# Explorer.net
KiCad netlist of a schematic drawn in EAGLE
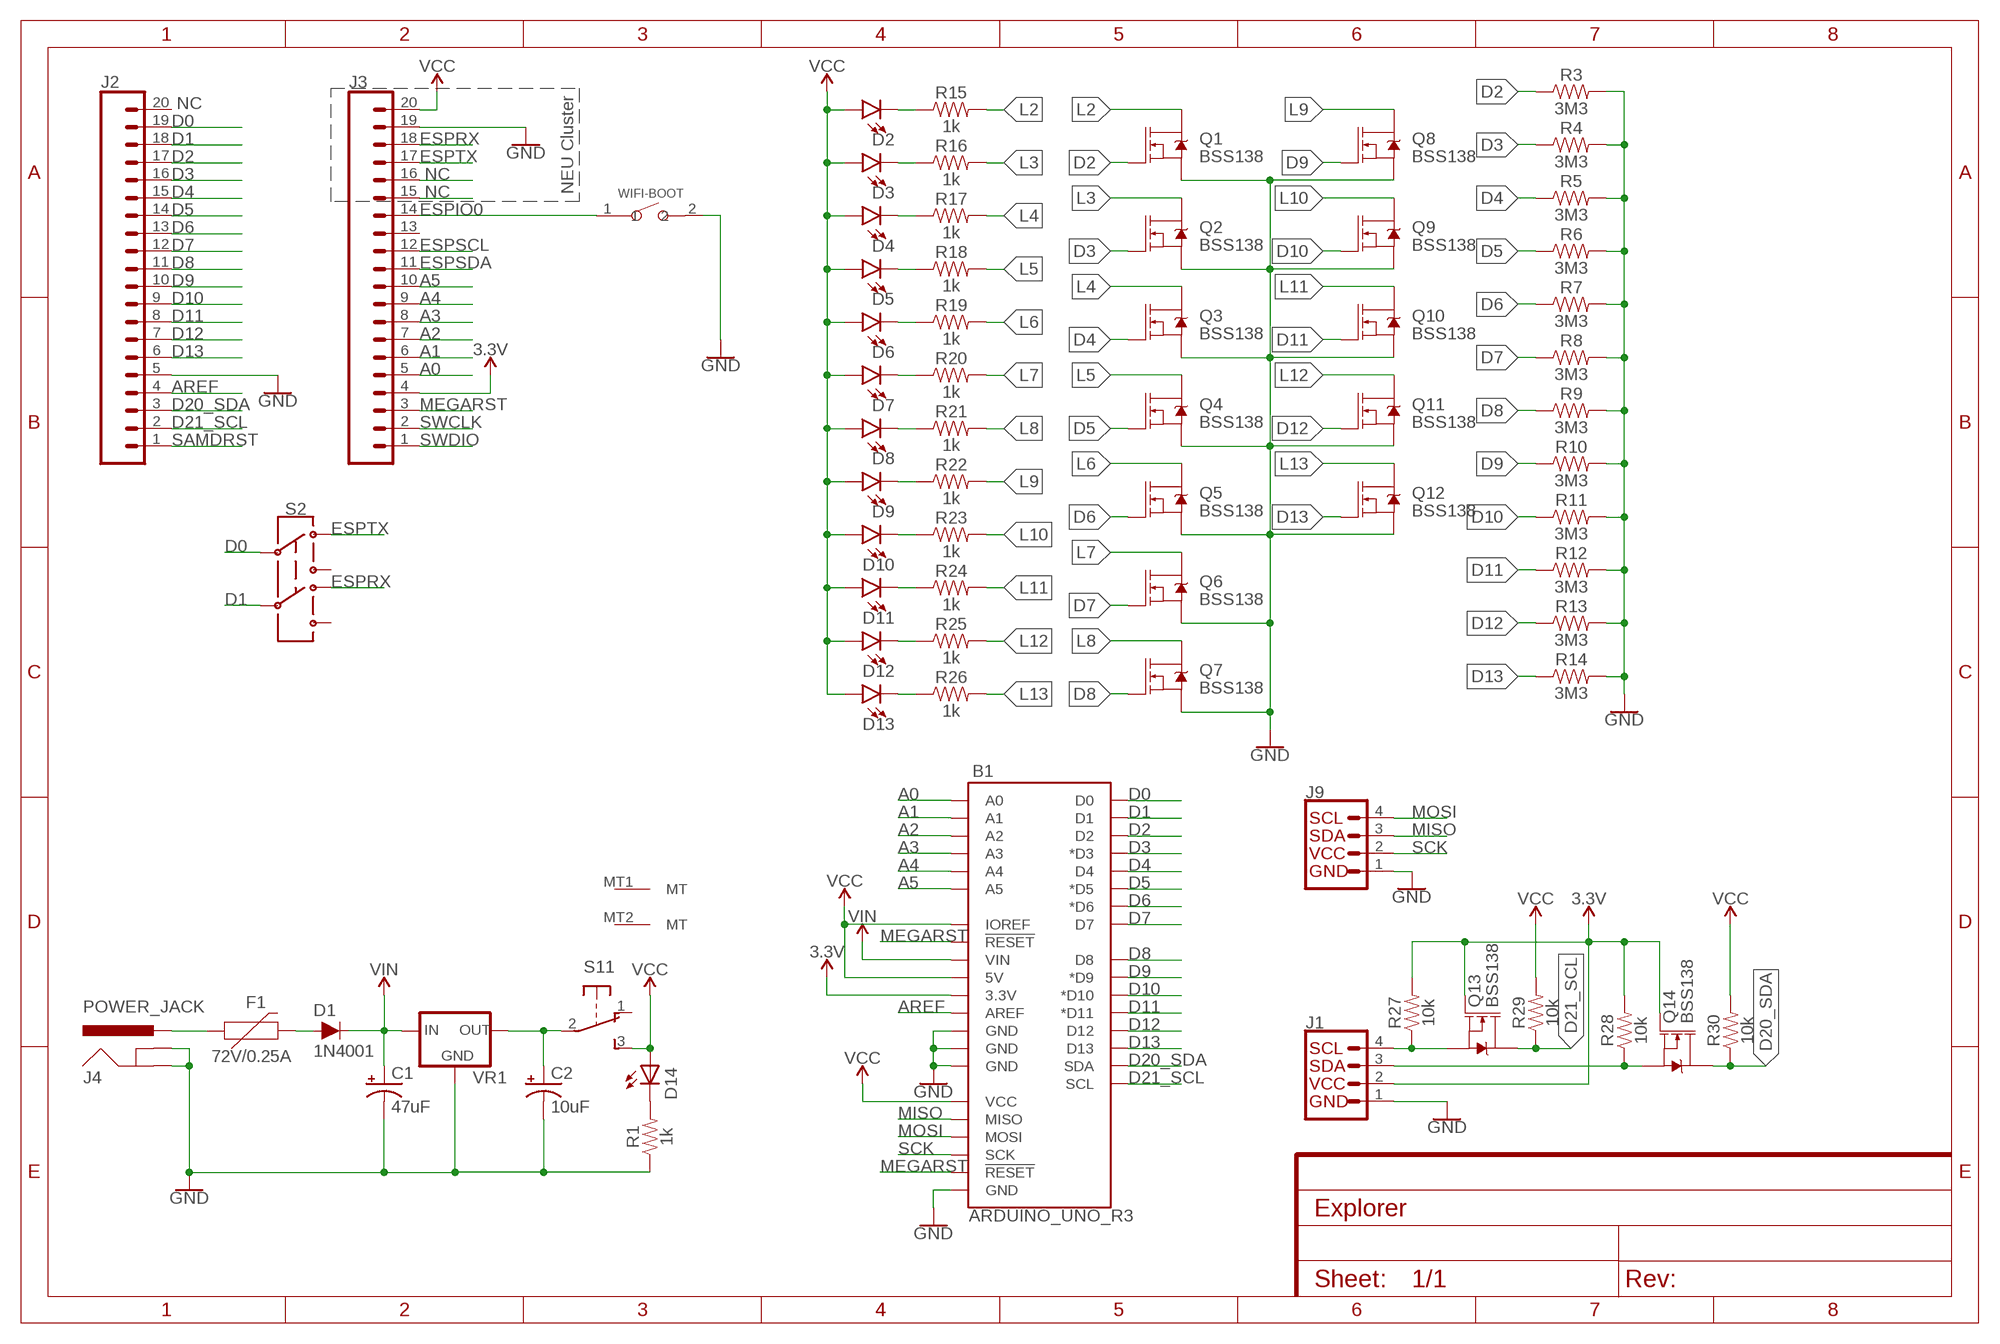
[diagram p0: schematic, sheet 1]

(export (version "E")
  (design (tool "Eeschema 10.0.6"))
  (components
    (comp (ref "B1")
      (value "ARDUINO_UNO_R3")
      (footprint "eagle-import:ARDUINO_R3")
      (libsource (lib "eagle-import") (part "ARDUINO_UNO_R3"))
    )
    (comp (ref "C1")
      (value "47uF")
      (footprint "eagle-import:CPOL-RADIAL-2.5MM-6.5MM")
      (libsource (lib "eagle-import") (part "100UF-POLAR-RADIAL-2.5MM-25V-20%"))
    )
    (comp (ref "C2")
      (value "10uF")
      (footprint "eagle-import:CPOL-RADIAL-2.5MM-6.5MM")
      (libsource (lib "eagle-import") (part "100UF-POLAR-RADIAL-2.5MM-25V-20%"))
    )
    (comp (ref "D1")
      (value "1N4001")
      (footprint "eagle-import:DIODE-1N4001-KIT")
      (libsource (lib "eagle-import") (part "DIODE-KIT2"))
    )
    (comp (ref "D2")
      (value "LED0603")
      (footprint "eagle-import:LED-0603")
      (fields (field (name "LCSC_PART") "C2286"))
      (libsource (lib "eagle-import") (part "LED0603"))
    )
    (comp (ref "D3")
      (value "LED0603")
      (footprint "eagle-import:LED-0603")
      (fields (field (name "LCSC_PART") "C2286"))
      (libsource (lib "eagle-import") (part "LED0603"))
    )
    (comp (ref "D4")
      (value "LED0603")
      (footprint "eagle-import:LED-0603")
      (fields (field (name "LCSC_PART") "C2286"))
      (libsource (lib "eagle-import") (part "LED0603"))
    )
    (comp (ref "D5")
      (value "LED0603")
      (footprint "eagle-import:LED-0603")
      (fields (field (name "LCSC_PART") "C2286"))
      (libsource (lib "eagle-import") (part "LED0603"))
    )
    (comp (ref "D6")
      (value "LED0603")
      (footprint "eagle-import:LED-0603")
      (fields (field (name "LCSC_PART") "C2286"))
      (libsource (lib "eagle-import") (part "LED0603"))
    )
    (comp (ref "D7")
      (value "LED0603")
      (footprint "eagle-import:LED-0603")
      (fields (field (name "LCSC_PART") "C2286"))
      (libsource (lib "eagle-import") (part "LED0603"))
    )
    (comp (ref "D8")
      (value "LED0603")
      (footprint "eagle-import:LED-0603")
      (fields (field (name "LCSC_PART") "C2286"))
      (libsource (lib "eagle-import") (part "LED0603"))
    )
    (comp (ref "D9")
      (value "LED0603")
      (footprint "eagle-import:LED-0603")
      (fields (field (name "LCSC_PART") "C2286"))
      (libsource (lib "eagle-import") (part "LED0603"))
    )
    (comp (ref "D10")
      (value "LED0603")
      (footprint "eagle-import:LED-0603")
      (fields (field (name "LCSC_PART") "C2286"))
      (libsource (lib "eagle-import") (part "LED0603"))
    )
    (comp (ref "D11")
      (value "LED0603")
      (footprint "eagle-import:LED-0603")
      (fields (field (name "LCSC_PART") "C2286"))
      (libsource (lib "eagle-import") (part "LED0603"))
    )
    (comp (ref "D12")
      (value "LED0603")
      (footprint "eagle-import:LED-0603")
      (fields (field (name "LCSC_PART") "C2286"))
      (libsource (lib "eagle-import") (part "LED0603"))
    )
    (comp (ref "D13")
      (value "LED0603")
      (footprint "eagle-import:LED-0603")
      (fields (field (name "LCSC_PART") "C2286"))
      (libsource (lib "eagle-import") (part "LED0603"))
    )
    (comp (ref "D14")
      (value "LEDCHIPLED_0805")
      (footprint "eagle-import:CHIPLED_0805")
      (fields (field (name "LCSC_PART") "C2296"))
      (libsource (lib "eagle-import") (part "LEDCHIPLED_0805"))
    )
    (comp (ref "F1")
      (value "72V/0.25A")
      (footprint "eagle-import:PTH")
      (libsource (lib "eagle-import") (part "PPTC_PTH"))
    )
    (comp (ref "J1")
      (value "QWIIC_CONNECTORJS-1MM")
      (footprint "eagle-import:1X04_1MM_RA")
      (fields (field (name "LCSC_PART") "C239522"))
      (libsource (lib "eagle-import") (part "QWIIC_CONNECTORJS-1MM"))
    )
    (comp (ref "J2")
      (value "CONN_20")
      (footprint "eagle-import:1X20")
      (fields (field (name "LCSC_PART") "C50984"))
      (libsource (lib "eagle-import") (part "CONN_20"))
    )
    (comp (ref "J3")
      (value "CONN_20")
      (footprint "eagle-import:1X20")
      (fields (field (name "LCSC_PART") "C50984"))
      (libsource (lib "eagle-import") (part "CONN_20"))
    )
    (comp (ref "J4")
      (value "POWER_JACK")
      (footprint "eagle-import:POWER_JACK_PTH")
      (libsource (lib "eagle-import") (part "POWER_JACK"))
    )
    (comp (ref "J9")
      (value "QWIIC_CONNECTORJS-1MM")
      (footprint "eagle-import:1X04_1MM_RA")
      (fields (field (name "LCSC_PART") "C239522"))
      (libsource (lib "eagle-import") (part "QWIIC_CONNECTORJS-1MM"))
    )
    (comp (ref "Q1")
      (value "BSS138")
      (footprint "eagle-import:SOT23-3")
      (fields (field (name "LCSC_PART") "C435876"))
      (libsource (lib "eagle-import") (part "MOSFET-NCH-BSS138"))
    )
    (comp (ref "Q2")
      (value "BSS138")
      (footprint "eagle-import:SOT23-3")
      (fields (field (name "LCSC_PART") "C435876"))
      (libsource (lib "eagle-import") (part "MOSFET-NCH-BSS138"))
    )
    (comp (ref "Q3")
      (value "BSS138")
      (footprint "eagle-import:SOT23-3")
      (fields (field (name "LCSC_PART") "C435876"))
      (libsource (lib "eagle-import") (part "MOSFET-NCH-BSS138"))
    )
    (comp (ref "Q4")
      (value "BSS138")
      (footprint "eagle-import:SOT23-3")
      (fields (field (name "LCSC_PART") "C435876"))
      (libsource (lib "eagle-import") (part "MOSFET-NCH-BSS138"))
    )
    (comp (ref "Q5")
      (value "BSS138")
      (footprint "eagle-import:SOT23-3")
      (fields (field (name "LCSC_PART") "C435876"))
      (libsource (lib "eagle-import") (part "MOSFET-NCH-BSS138"))
    )
    (comp (ref "Q6")
      (value "BSS138")
      (footprint "eagle-import:SOT23-3")
      (fields (field (name "LCSC_PART") "C435876"))
      (libsource (lib "eagle-import") (part "MOSFET-NCH-BSS138"))
    )
    (comp (ref "Q7")
      (value "BSS138")
      (footprint "eagle-import:SOT23-3")
      (fields (field (name "LCSC_PART") "C435876"))
      (libsource (lib "eagle-import") (part "MOSFET-NCH-BSS138"))
    )
    (comp (ref "Q8")
      (value "BSS138")
      (footprint "eagle-import:SOT23-3")
      (fields (field (name "LCSC_PART") "C435876"))
      (libsource (lib "eagle-import") (part "MOSFET-NCH-BSS138"))
    )
    (comp (ref "Q9")
      (value "BSS138")
      (footprint "eagle-import:SOT23-3")
      (fields (field (name "LCSC_PART") "C435876"))
      (libsource (lib "eagle-import") (part "MOSFET-NCH-BSS138"))
    )
    (comp (ref "Q10")
      (value "BSS138")
      (footprint "eagle-import:SOT23-3")
      (fields (field (name "LCSC_PART") "C435876"))
      (libsource (lib "eagle-import") (part "MOSFET-NCH-BSS138"))
    )
    (comp (ref "Q11")
      (value "BSS138")
      (footprint "eagle-import:SOT23-3")
      (fields (field (name "LCSC_PART") "C435876"))
      (libsource (lib "eagle-import") (part "MOSFET-NCH-BSS138"))
    )
    (comp (ref "Q12")
      (value "BSS138")
      (footprint "eagle-import:SOT23-3")
      (fields (field (name "LCSC_PART") "C435876"))
      (libsource (lib "eagle-import") (part "MOSFET-NCH-BSS138"))
    )
    (comp (ref "Q13")
      (value "BSS138")
      (footprint "eagle-import:SOT23-3")
      (fields (field (name "LCSC_PART") "C435876"))
      (libsource (lib "eagle-import") (part "MOSFET-NCH-BSS138"))
    )
    (comp (ref "Q14")
      (value "BSS138")
      (footprint "eagle-import:SOT23-3")
      (fields (field (name "LCSC_PART") "C435876"))
      (libsource (lib "eagle-import") (part "MOSFET-NCH-BSS138"))
    )
    (comp (ref "R1")
      (value "1k")
      (footprint "eagle-import:0603")
      (fields (field (name "LCSC_PART") "C21190"))
      (libsource (lib "eagle-import") (part "RESISTOR0603"))
    )
    (comp (ref "R3")
      (value "3M3")
      (footprint "eagle-import:0603")
      (fields (field (name "LCSC_PART") "C103556"))
      (libsource (lib "eagle-import") (part "RESISTOR0603"))
    )
    (comp (ref "R4")
      (value "3M3")
      (footprint "eagle-import:0603")
      (fields (field (name "LCSC_PART") "C103556"))
      (libsource (lib "eagle-import") (part "RESISTOR0603"))
    )
    (comp (ref "R5")
      (value "3M3")
      (footprint "eagle-import:0603")
      (fields (field (name "LCSC_PART") "C103556"))
      (libsource (lib "eagle-import") (part "RESISTOR0603"))
    )
    (comp (ref "R6")
      (value "3M3")
      (footprint "eagle-import:0603")
      (fields (field (name "LCSC_PART") "C103556"))
      (libsource (lib "eagle-import") (part "RESISTOR0603"))
    )
    (comp (ref "R7")
      (value "3M3")
      (footprint "eagle-import:0603")
      (fields (field (name "LCSC_PART") "C103556"))
      (libsource (lib "eagle-import") (part "RESISTOR0603"))
    )
    (comp (ref "R8")
      (value "3M3")
      (footprint "eagle-import:0603")
      (fields (field (name "LCSC_PART") "C103556"))
      (libsource (lib "eagle-import") (part "RESISTOR0603"))
    )
    (comp (ref "R9")
      (value "3M3")
      (footprint "eagle-import:0603")
      (fields (field (name "LCSC_PART") "C103556"))
      (libsource (lib "eagle-import") (part "RESISTOR0603"))
    )
    (comp (ref "R10")
      (value "3M3")
      (footprint "eagle-import:0603")
      (fields (field (name "LCSC_PART") "C103556"))
      (libsource (lib "eagle-import") (part "RESISTOR0603"))
    )
    (comp (ref "R11")
      (value "3M3")
      (footprint "eagle-import:0603")
      (fields (field (name "LCSC_PART") "C103556"))
      (libsource (lib "eagle-import") (part "RESISTOR0603"))
    )
    (comp (ref "R12")
      (value "3M3")
      (footprint "eagle-import:0603")
      (fields (field (name "LCSC_PART") "C103556"))
      (libsource (lib "eagle-import") (part "RESISTOR0603"))
    )
    (comp (ref "R13")
      (value "3M3")
      (footprint "eagle-import:0603")
      (fields (field (name "LCSC_PART") "C103556"))
      (libsource (lib "eagle-import") (part "RESISTOR0603"))
    )
    (comp (ref "R14")
      (value "3M3")
      (footprint "eagle-import:0603")
      (fields (field (name "LCSC_PART") "C103556"))
      (libsource (lib "eagle-import") (part "RESISTOR0603"))
    )
    (comp (ref "R15")
      (value "1k")
      (footprint "eagle-import:0603")
      (fields (field (name "LCSC_PART") "C21190"))
      (libsource (lib "eagle-import") (part "10KOHM-0603-1/10W-1%"))
    )
    (comp (ref "R16")
      (value "1k")
      (footprint "eagle-import:0603")
      (fields (field (name "LCSC_PART") "C21190"))
      (libsource (lib "eagle-import") (part "10KOHM-0603-1/10W-1%"))
    )
    (comp (ref "R17")
      (value "1k")
      (footprint "eagle-import:0603")
      (fields (field (name "LCSC_PART") "C21190"))
      (libsource (lib "eagle-import") (part "10KOHM-0603-1/10W-1%"))
    )
    (comp (ref "R18")
      (value "1k")
      (footprint "eagle-import:0603")
      (fields (field (name "LCSC_PART") "C21190"))
      (libsource (lib "eagle-import") (part "10KOHM-0603-1/10W-1%"))
    )
    (comp (ref "R19")
      (value "1k")
      (footprint "eagle-import:0603")
      (fields (field (name "LCSC_PART") "C21190"))
      (libsource (lib "eagle-import") (part "10KOHM-0603-1/10W-1%"))
    )
    (comp (ref "R20")
      (value "1k")
      (footprint "eagle-import:0603")
      (fields (field (name "LCSC_PART") "C21190"))
      (libsource (lib "eagle-import") (part "10KOHM-0603-1/10W-1%"))
    )
    (comp (ref "R21")
      (value "1k")
      (footprint "eagle-import:0603")
      (fields (field (name "LCSC_PART") "C21190"))
      (libsource (lib "eagle-import") (part "10KOHM-0603-1/10W-1%"))
    )
    (comp (ref "R22")
      (value "1k")
      (footprint "eagle-import:0603")
      (fields (field (name "LCSC_PART") "C21190"))
      (libsource (lib "eagle-import") (part "10KOHM-0603-1/10W-1%"))
    )
    (comp (ref "R23")
      (value "1k")
      (footprint "eagle-import:0603")
      (fields (field (name "LCSC_PART") "C21190"))
      (libsource (lib "eagle-import") (part "10KOHM-0603-1/10W-1%"))
    )
    (comp (ref "R24")
      (value "1k")
      (footprint "eagle-import:0603")
      (fields (field (name "LCSC_PART") "C21190"))
      (libsource (lib "eagle-import") (part "10KOHM-0603-1/10W-1%"))
    )
    (comp (ref "R25")
      (value "1k")
      (footprint "eagle-import:0603")
      (fields (field (name "LCSC_PART") "C21190"))
      (libsource (lib "eagle-import") (part "10KOHM-0603-1/10W-1%"))
    )
    (comp (ref "R26")
      (value "1k")
      (footprint "eagle-import:0603")
      (fields (field (name "LCSC_PART") "C21190"))
      (libsource (lib "eagle-import") (part "10KOHM-0603-1/10W-1%"))
    )
    (comp (ref "R27")
      (value "10k")
      (footprint "eagle-import:0603")
      (fields (field (name "LCSC_PART") "C25804"))
      (libsource (lib "eagle-import") (part "10KOHM-0603-1/10W-1%"))
    )
    (comp (ref "R28")
      (value "10k")
      (footprint "eagle-import:0603")
      (fields (field (name "LCSC_PART") "C25804"))
      (libsource (lib "eagle-import") (part "10KOHM-0603-1/10W-1%"))
    )
    (comp (ref "R29")
      (value "10k")
      (footprint "eagle-import:0603")
      (fields (field (name "LCSC_PART") "C25804"))
      (libsource (lib "eagle-import") (part "10KOHM-0603-1/10W-1%"))
    )
    (comp (ref "R30")
      (value "10k")
      (footprint "eagle-import:0603")
      (fields (field (name "LCSC_PART") "C25804"))
      (libsource (lib "eagle-import") (part "10KOHM-0603-1/10W-1%"))
    )
    (comp (ref "S1")
      (value "EG1213")
      (footprint "eagle-import:EG1213")
      (libsource (lib "eagle-import") (part "EG1213"))
    )
    (comp (ref "S2")
      (value "SWITCH-DPDT-SMD-AYZ0202")
      (footprint "eagle-import:SWITCH_DPDT_SMD_AYZ0202")
      (fields (field (name "LCSC_PART") "C318999"))
      (libsource (lib "eagle-import") (part "SWITCH-DPDT-SMD-AYZ0202"))
    )
    (comp (ref "VR1")
      (value "V_REG_78XXSINK")
      (footprint "eagle-import:TO220-IGO")
      (libsource (lib "eagle-import") (part "V_REG_78XXSINK"))
    )
    (comp (ref "WIFI-BOOT")
      (value "SKRKAEE020")
      (footprint "eagle-import:SW2-2.6-3.9X2.9X1.5+0.4MM")
      (fields (field (name "LCSC_PART") "C115357") (field (name "LCSC_PART_1") "C455280"))
      (libsource (lib "eagle-import") (part "SMD-BUTTON(2P-3.9X2.9X1.5+0.4MM)-SKRKAEE020"))
    )
  )
  (nets
    (net (code "1") (name "/A0") (class "Default")
      (node (ref "B1") (pin "A0") (pinfunction "A0_A0") (pintype "bidirectional"))
      (node (ref "J3") (pin "5") (pinfunction "5_5") (pintype "passive"))
    )
    (net (code "2") (name "/A1") (class "Default")
      (node (ref "B1") (pin "A1") (pinfunction "A1_A1") (pintype "bidirectional"))
      (node (ref "J3") (pin "6") (pinfunction "6_6") (pintype "passive"))
    )
    (net (code "3") (name "/A2") (class "Default")
      (node (ref "B1") (pin "A2") (pinfunction "A2_A2") (pintype "bidirectional"))
      (node (ref "J3") (pin "7") (pinfunction "7_7") (pintype "passive"))
    )
    (net (code "4") (name "/A3") (class "Default")
      (node (ref "B1") (pin "A3") (pinfunction "A3_A3") (pintype "bidirectional"))
      (node (ref "J3") (pin "8") (pinfunction "8_8") (pintype "passive"))
    )
    (net (code "5") (name "/A4") (class "Default")
      (node (ref "B1") (pin "A4") (pinfunction "A4_A4") (pintype "bidirectional"))
      (node (ref "J3") (pin "9") (pinfunction "9_9") (pintype "passive"))
    )
    (net (code "6") (name "/A5") (class "Default")
      (node (ref "B1") (pin "A5") (pinfunction "A5_A5") (pintype "bidirectional"))
      (node (ref "J3") (pin "10") (pinfunction "10_10") (pintype "passive"))
    )
    (net (code "7") (name "/AREF") (class "Default")
      (node (ref "B1") (pin "AREF") (pinfunction "AREF_AREF") (pintype "bidirectional"))
      (node (ref "J2") (pin "4") (pinfunction "4_4") (pintype "passive"))
    )
    (net (code "8") (name "/D0") (class "Default")
      (node (ref "B1") (pin "D0") (pinfunction "D0_D0") (pintype "bidirectional"))
      (node (ref "J2") (pin "19") (pinfunction "19_19") (pintype "passive"))
      (node (ref "S2") (pin "2") (pinfunction "2_2") (pintype "bidirectional"))
    )
    (net (code "9") (name "/D1") (class "Default")
      (node (ref "B1") (pin "D1") (pinfunction "D1_D1") (pintype "bidirectional"))
      (node (ref "J2") (pin "18") (pinfunction "18_18") (pintype "passive"))
      (node (ref "S2") (pin "5") (pinfunction "5_5") (pintype "bidirectional"))
    )
    (net (code "10") (name "/ESPIO0") (class "Default")
      (node (ref "J3") (pin "14") (pinfunction "14_14") (pintype "passive"))
      (node (ref "WIFI-BOOT") (pin "1") (pinfunction "1_1") (pintype "bidirectional"))
    )
    (net (code "11") (name "/ESPRX") (class "Default")
      (node (ref "J3") (pin "18") (pinfunction "18_18") (pintype "passive"))
      (node (ref "S2") (pin "4") (pinfunction "4_4") (pintype "bidirectional"))
    )
    (net (code "12") (name "/ESPSCL") (class "Default")
      (node (ref "J3") (pin "12") (pinfunction "12_12") (pintype "passive"))
    )
    (net (code "13") (name "/ESPSDA") (class "Default")
      (node (ref "J3") (pin "11") (pinfunction "11_11") (pintype "passive"))
    )
    (net (code "14") (name "/ESPTX") (class "Default")
      (node (ref "J3") (pin "17") (pinfunction "17_17") (pintype "passive"))
      (node (ref "S2") (pin "1") (pinfunction "1_1") (pintype "bidirectional"))
    )
    (net (code "15") (name "/MEGARST") (class "Default")
      (node (ref "B1") (pin "RESET@1") (pinfunction "~{RESET}_RESET@1") (pintype "bidirectional"))
      (node (ref "B1") (pin "RESET@2") (pinfunction "~{RESET}_RESET@2") (pintype "bidirectional"))
      (node (ref "J3") (pin "3") (pinfunction "3_3") (pintype "passive"))
    )
    (net (code "16") (name "/MISO") (class "Default")
      (node (ref "B1") (pin "MISO") (pinfunction "MISO_MISO") (pintype "bidirectional"))
      (node (ref "J9") (pin "3") (pinfunction "SDA_3") (pintype "passive"))
    )
    (net (code "17") (name "/MOSI") (class "Default")
      (node (ref "B1") (pin "MOSI") (pinfunction "MOSI_MOSI") (pintype "bidirectional"))
      (node (ref "J9") (pin "4") (pinfunction "SCL_4") (pintype "passive"))
    )
    (net (code "18") (name "/SAMDRST") (class "Default")
      (node (ref "J2") (pin "1") (pinfunction "1_1") (pintype "passive"))
    )
    (net (code "19") (name "/SCK") (class "Default")
      (node (ref "B1") (pin "SCK") (pinfunction "SCK_SCK") (pintype "bidirectional"))
      (node (ref "J9") (pin "2") (pinfunction "VCC_2") (pintype "power_in"))
    )
    (net (code "20") (name "/SWCLK") (class "Default")
      (node (ref "J3") (pin "2") (pinfunction "2_2") (pintype "passive"))
    )
    (net (code "21") (name "/SWDIO") (class "Default")
      (node (ref "J3") (pin "1") (pinfunction "1_1") (pintype "passive"))
    )
    (net (code "22") (name "3.3V") (class "Default")
      (node (ref "B1") (pin "3.3V") (pinfunction "3.3V_3.3V") (pintype "bidirectional"))
      (node (ref "J1") (pin "2") (pinfunction "VCC_2") (pintype "power_in"))
      (node (ref "J3") (pin "4") (pinfunction "4_4") (pintype "passive"))
      (node (ref "Q13") (pin "1") (pinfunction "G_1") (pintype "bidirectional"))
      (node (ref "Q14") (pin "1") (pinfunction "G_1") (pintype "bidirectional"))
      (node (ref "R27") (pin "2") (pinfunction "2_2") (pintype "passive"))
      (node (ref "R28") (pin "2") (pinfunction "2_2") (pintype "passive"))
    )
    (net (code "23") (name "D2") (class "Default")
      (node (ref "B1") (pin "D2") (pinfunction "D2_D2") (pintype "bidirectional"))
      (node (ref "J2") (pin "17") (pinfunction "17_17") (pintype "passive"))
      (node (ref "Q1") (pin "1") (pinfunction "G_1") (pintype "bidirectional"))
      (node (ref "R3") (pin "1") (pinfunction "1_1") (pintype "passive"))
    )
    (net (code "24") (name "D3") (class "Default")
      (node (ref "B1") (pin "D3") (pinfunction "*D3_D3") (pintype "bidirectional"))
      (node (ref "J2") (pin "16") (pinfunction "16_16") (pintype "passive"))
      (node (ref "Q2") (pin "1") (pinfunction "G_1") (pintype "bidirectional"))
      (node (ref "R4") (pin "1") (pinfunction "1_1") (pintype "passive"))
    )
    (net (code "25") (name "D4") (class "Default")
      (node (ref "B1") (pin "D4") (pinfunction "D4_D4") (pintype "bidirectional"))
      (node (ref "J2") (pin "15") (pinfunction "15_15") (pintype "passive"))
      (node (ref "Q3") (pin "1") (pinfunction "G_1") (pintype "bidirectional"))
      (node (ref "R5") (pin "1") (pinfunction "1_1") (pintype "passive"))
    )
    (net (code "26") (name "D5") (class "Default")
      (node (ref "B1") (pin "D5") (pinfunction "*D5_D5") (pintype "bidirectional"))
      (node (ref "J2") (pin "14") (pinfunction "14_14") (pintype "passive"))
      (node (ref "Q4") (pin "1") (pinfunction "G_1") (pintype "bidirectional"))
      (node (ref "R6") (pin "1") (pinfunction "1_1") (pintype "passive"))
    )
    (net (code "27") (name "D6") (class "Default")
      (node (ref "B1") (pin "D6") (pinfunction "*D6_D6") (pintype "bidirectional"))
      (node (ref "J2") (pin "13") (pinfunction "13_13") (pintype "passive"))
      (node (ref "Q5") (pin "1") (pinfunction "G_1") (pintype "bidirectional"))
      (node (ref "R7") (pin "1") (pinfunction "1_1") (pintype "passive"))
    )
    (net (code "28") (name "D7") (class "Default")
      (node (ref "B1") (pin "D7") (pinfunction "D7_D7") (pintype "bidirectional"))
      (node (ref "J2") (pin "12") (pinfunction "12_12") (pintype "passive"))
      (node (ref "Q6") (pin "1") (pinfunction "G_1") (pintype "bidirectional"))
      (node (ref "R8") (pin "1") (pinfunction "1_1") (pintype "passive"))
    )
    (net (code "29") (name "D8") (class "Default")
      (node (ref "B1") (pin "D8") (pinfunction "D8_D8") (pintype "bidirectional"))
      (node (ref "J2") (pin "11") (pinfunction "11_11") (pintype "passive"))
      (node (ref "Q7") (pin "1") (pinfunction "G_1") (pintype "bidirectional"))
      (node (ref "R9") (pin "1") (pinfunction "1_1") (pintype "passive"))
    )
    (net (code "30") (name "D9") (class "Default")
      (node (ref "B1") (pin "D9") (pinfunction "*D9_D9") (pintype "bidirectional"))
      (node (ref "J2") (pin "10") (pinfunction "10_10") (pintype "passive"))
      (node (ref "Q8") (pin "1") (pinfunction "G_1") (pintype "bidirectional"))
      (node (ref "R10") (pin "1") (pinfunction "1_1") (pintype "passive"))
    )
    (net (code "31") (name "D10") (class "Default")
      (node (ref "B1") (pin "D10") (pinfunction "*D10_D10") (pintype "bidirectional"))
      (node (ref "J2") (pin "9") (pinfunction "9_9") (pintype "passive"))
      (node (ref "Q9") (pin "1") (pinfunction "G_1") (pintype "bidirectional"))
      (node (ref "R11") (pin "1") (pinfunction "1_1") (pintype "passive"))
    )
    (net (code "32") (name "D11") (class "Default")
      (node (ref "B1") (pin "D11") (pinfunction "*D11_D11") (pintype "bidirectional"))
      (node (ref "J2") (pin "8") (pinfunction "8_8") (pintype "passive"))
      (node (ref "Q10") (pin "1") (pinfunction "G_1") (pintype "bidirectional"))
      (node (ref "R12") (pin "1") (pinfunction "1_1") (pintype "passive"))
    )
    (net (code "33") (name "D12") (class "Default")
      (node (ref "B1") (pin "D12") (pinfunction "D12_D12") (pintype "bidirectional"))
      (node (ref "J2") (pin "7") (pinfunction "7_7") (pintype "passive"))
      (node (ref "Q11") (pin "1") (pinfunction "G_1") (pintype "bidirectional"))
      (node (ref "R13") (pin "1") (pinfunction "1_1") (pintype "passive"))
    )
    (net (code "34") (name "D13") (class "Default")
      (node (ref "B1") (pin "D13") (pinfunction "D13_D13") (pintype "bidirectional"))
      (node (ref "J2") (pin "6") (pinfunction "6_6") (pintype "passive"))
      (node (ref "Q12") (pin "1") (pinfunction "G_1") (pintype "bidirectional"))
      (node (ref "R14") (pin "1") (pinfunction "1_1") (pintype "passive"))
    )
    (net (code "35") (name "D20_SDA") (class "Default")
      (node (ref "B1") (pin "SDA") (pinfunction "SDA_SDA") (pintype "bidirectional"))
      (node (ref "J2") (pin "3") (pinfunction "3_3") (pintype "passive"))
      (node (ref "Q14") (pin "3") (pinfunction "D_3") (pintype "bidirectional"))
      (node (ref "R30") (pin "1") (pinfunction "1_1") (pintype "passive"))
    )
    (net (code "36") (name "D21_SCL") (class "Default")
      (node (ref "B1") (pin "SCL") (pinfunction "SCL_SCL") (pintype "bidirectional"))
      (node (ref "J2") (pin "2") (pinfunction "2_2") (pintype "passive"))
      (node (ref "Q13") (pin "3") (pinfunction "D_3") (pintype "bidirectional"))
      (node (ref "R29") (pin "1") (pinfunction "1_1") (pintype "passive"))
    )
    (net (code "37") (name "GND") (class "Default")
      (node (ref "B1") (pin "GND@1") (pinfunction "GND_GND@1") (pintype "bidirectional"))
      (node (ref "B1") (pin "GND@2") (pinfunction "GND_GND@2") (pintype "bidirectional"))
      (node (ref "B1") (pin "GND@3") (pinfunction "GND_GND@3") (pintype "bidirectional"))
      (node (ref "B1") (pin "GND@4") (pinfunction "GND_GND@4") (pintype "bidirectional"))
      (node (ref "C1") (pin "2") (pinfunction "-_2") (pintype "passive"))
      (node (ref "C2") (pin "2") (pinfunction "-_2") (pintype "passive"))
      (node (ref "J1") (pin "1") (pinfunction "GND_1") (pintype "power_in"))
      (node (ref "J2") (pin "5") (pinfunction "5_5") (pintype "passive"))
      (node (ref "J3") (pin "19") (pinfunction "19_19") (pintype "passive"))
      (node (ref "J4") (pin "GND") (pinfunction "GND_GND") (pintype "bidirectional"))
      (node (ref "J4") (pin "GNDBREAK") (pinfunction "GNDBREAK_GNDBREAK") (pintype "bidirectional"))
      (node (ref "J9") (pin "1") (pinfunction "GND_1") (pintype "power_in"))
      (node (ref "Q1") (pin "2") (pinfunction "S_2") (pintype "bidirectional"))
      (node (ref "Q10") (pin "2") (pinfunction "S_2") (pintype "bidirectional"))
      (node (ref "Q11") (pin "2") (pinfunction "S_2") (pintype "bidirectional"))
      (node (ref "Q12") (pin "2") (pinfunction "S_2") (pintype "bidirectional"))
      (node (ref "Q2") (pin "2") (pinfunction "S_2") (pintype "bidirectional"))
      (node (ref "Q3") (pin "2") (pinfunction "S_2") (pintype "bidirectional"))
      (node (ref "Q4") (pin "2") (pinfunction "S_2") (pintype "bidirectional"))
      (node (ref "Q5") (pin "2") (pinfunction "S_2") (pintype "bidirectional"))
      (node (ref "Q6") (pin "2") (pinfunction "S_2") (pintype "bidirectional"))
      (node (ref "Q7") (pin "2") (pinfunction "S_2") (pintype "bidirectional"))
      (node (ref "Q8") (pin "2") (pinfunction "S_2") (pintype "bidirectional"))
      (node (ref "Q9") (pin "2") (pinfunction "S_2") (pintype "bidirectional"))
      (node (ref "R1") (pin "1") (pinfunction "1_1") (pintype "passive"))
      (node (ref "R10") (pin "2") (pinfunction "2_2") (pintype "passive"))
      (node (ref "R11") (pin "2") (pinfunction "2_2") (pintype "passive"))
      (node (ref "R12") (pin "2") (pinfunction "2_2") (pintype "passive"))
      (node (ref "R13") (pin "2") (pinfunction "2_2") (pintype "passive"))
      (node (ref "R14") (pin "2") (pinfunction "2_2") (pintype "passive"))
      (node (ref "R3") (pin "2") (pinfunction "2_2") (pintype "passive"))
      (node (ref "R4") (pin "2") (pinfunction "2_2") (pintype "passive"))
      (node (ref "R5") (pin "2") (pinfunction "2_2") (pintype "passive"))
      (node (ref "R6") (pin "2") (pinfunction "2_2") (pintype "passive"))
      (node (ref "R7") (pin "2") (pinfunction "2_2") (pintype "passive"))
      (node (ref "R8") (pin "2") (pinfunction "2_2") (pintype "passive"))
      (node (ref "R9") (pin "2") (pinfunction "2_2") (pintype "passive"))
      (node (ref "VR1") (pin "GND") (pinfunction "GND_GND") (pintype "input"))
      (node (ref "WIFI-BOOT") (pin "2") (pinfunction "2_2") (pintype "bidirectional"))
    )
    (net (code "38") (name "L2") (class "Default")
      (node (ref "Q1") (pin "3") (pinfunction "D_3") (pintype "bidirectional"))
      (node (ref "R15") (pin "2") (pinfunction "2_2") (pintype "passive"))
    )
    (net (code "39") (name "L3") (class "Default")
      (node (ref "Q2") (pin "3") (pinfunction "D_3") (pintype "bidirectional"))
      (node (ref "R16") (pin "2") (pinfunction "2_2") (pintype "passive"))
    )
    (net (code "40") (name "L4") (class "Default")
      (node (ref "Q3") (pin "3") (pinfunction "D_3") (pintype "bidirectional"))
      (node (ref "R17") (pin "2") (pinfunction "2_2") (pintype "passive"))
    )
    (net (code "41") (name "L5") (class "Default")
      (node (ref "Q4") (pin "3") (pinfunction "D_3") (pintype "bidirectional"))
      (node (ref "R18") (pin "2") (pinfunction "2_2") (pintype "passive"))
    )
    (net (code "42") (name "L6") (class "Default")
      (node (ref "Q5") (pin "3") (pinfunction "D_3") (pintype "bidirectional"))
      (node (ref "R19") (pin "2") (pinfunction "2_2") (pintype "passive"))
    )
    (net (code "43") (name "L7") (class "Default")
      (node (ref "Q6") (pin "3") (pinfunction "D_3") (pintype "bidirectional"))
      (node (ref "R20") (pin "2") (pinfunction "2_2") (pintype "passive"))
    )
    (net (code "44") (name "L8") (class "Default")
      (node (ref "Q7") (pin "3") (pinfunction "D_3") (pintype "bidirectional"))
      (node (ref "R21") (pin "2") (pinfunction "2_2") (pintype "passive"))
    )
    (net (code "45") (name "L9") (class "Default")
      (node (ref "Q8") (pin "3") (pinfunction "D_3") (pintype "bidirectional"))
      (node (ref "R22") (pin "2") (pinfunction "2_2") (pintype "passive"))
    )
    (net (code "46") (name "L10") (class "Default")
      (node (ref "Q9") (pin "3") (pinfunction "D_3") (pintype "bidirectional"))
      (node (ref "R23") (pin "2") (pinfunction "2_2") (pintype "passive"))
    )
    (net (code "47") (name "L11") (class "Default")
      (node (ref "Q10") (pin "3") (pinfunction "D_3") (pintype "bidirectional"))
      (node (ref "R24") (pin "2") (pinfunction "2_2") (pintype "passive"))
    )
    (net (code "48") (name "L12") (class "Default")
      (node (ref "Q11") (pin "3") (pinfunction "D_3") (pintype "bidirectional"))
      (node (ref "R25") (pin "2") (pinfunction "2_2") (pintype "passive"))
    )
    (net (code "49") (name "L13") (class "Default")
      (node (ref "Q12") (pin "3") (pinfunction "D_3") (pintype "bidirectional"))
      (node (ref "R26") (pin "2") (pinfunction "2_2") (pintype "passive"))
    )
    (net (code "50") (name "Net-(C2-+)") (class "Default")
      (node (ref "C2") (pin "1") (pinfunction "+_1") (pintype "passive"))
      (node (ref "S1") (pin "2") (pinfunction "P_2") (pintype "passive"))
      (node (ref "VR1") (pin "OUT") (pinfunction "OUT_OUT") (pintype "passive"))
    )
    (net (code "51") (name "Net-(D2-PadC)") (class "Default")
      (node (ref "D2") (pin "C") (pinfunction "C_C") (pintype "passive"))
      (node (ref "R15") (pin "1") (pinfunction "1_1") (pintype "passive"))
    )
    (net (code "52") (name "Net-(D3-PadC)") (class "Default")
      (node (ref "D3") (pin "C") (pinfunction "C_C") (pintype "passive"))
      (node (ref "R16") (pin "1") (pinfunction "1_1") (pintype "passive"))
    )
    (net (code "53") (name "Net-(D4-PadC)") (class "Default")
      (node (ref "D4") (pin "C") (pinfunction "C_C") (pintype "passive"))
      (node (ref "R17") (pin "1") (pinfunction "1_1") (pintype "passive"))
    )
    (net (code "54") (name "Net-(D5-PadC)") (class "Default")
      (node (ref "D5") (pin "C") (pinfunction "C_C") (pintype "passive"))
      (node (ref "R18") (pin "1") (pinfunction "1_1") (pintype "passive"))
    )
    (net (code "55") (name "Net-(D6-PadC)") (class "Default")
      (node (ref "D6") (pin "C") (pinfunction "C_C") (pintype "passive"))
      (node (ref "R19") (pin "1") (pinfunction "1_1") (pintype "passive"))
    )
    (net (code "56") (name "Net-(D7-PadC)") (class "Default")
      (node (ref "D7") (pin "C") (pinfunction "C_C") (pintype "passive"))
      (node (ref "R20") (pin "1") (pinfunction "1_1") (pintype "passive"))
    )
    (net (code "57") (name "Net-(D8-PadC)") (class "Default")
      (node (ref "D8") (pin "C") (pinfunction "C_C") (pintype "passive"))
      (node (ref "R21") (pin "1") (pinfunction "1_1") (pintype "passive"))
    )
    (net (code "58") (name "Net-(D9-PadC)") (class "Default")
      (node (ref "D9") (pin "C") (pinfunction "C_C") (pintype "passive"))
      (node (ref "R22") (pin "1") (pinfunction "1_1") (pintype "passive"))
    )
    (net (code "59") (name "Net-(D10-PadC)") (class "Default")
      (node (ref "D10") (pin "C") (pinfunction "C_C") (pintype "passive"))
      (node (ref "R23") (pin "1") (pinfunction "1_1") (pintype "passive"))
    )
    (net (code "60") (name "Net-(D11-PadC)") (class "Default")
      (node (ref "D11") (pin "C") (pinfunction "C_C") (pintype "passive"))
      (node (ref "R24") (pin "1") (pinfunction "1_1") (pintype "passive"))
    )
    (net (code "61") (name "Net-(D12-PadC)") (class "Default")
      (node (ref "D12") (pin "C") (pinfunction "C_C") (pintype "passive"))
      (node (ref "R25") (pin "1") (pinfunction "1_1") (pintype "passive"))
    )
    (net (code "62") (name "Net-(D13-PadC)") (class "Default")
      (node (ref "D13") (pin "C") (pinfunction "C_C") (pintype "passive"))
      (node (ref "R26") (pin "1") (pinfunction "1_1") (pintype "passive"))
    )
    (net (code "63") (name "Net-(D14-PadC)") (class "Default")
      (node (ref "D14") (pin "C") (pinfunction "C_C") (pintype "passive"))
      (node (ref "R1") (pin "2") (pinfunction "2_2") (pintype "passive"))
    )
    (net (code "64") (name "Net-(F1-1)") (class "Default")
      (node (ref "F1") (pin "P$1") (pinfunction "1_P$1") (pintype "bidirectional"))
      (node (ref "J4") (pin "PWR") (pinfunction "PWR_PWR") (pintype "bidirectional"))
    )
    (net (code "65") (name "Net-(F1-2)") (class "Default")
      (node (ref "D1") (pin "A") (pinfunction "A_A") (pintype "passive"))
      (node (ref "F1") (pin "P$2") (pinfunction "2_P$2") (pintype "bidirectional"))
    )
    (net (code "66") (name "Net-(J1-SCL)") (class "Default")
      (node (ref "J1") (pin "4") (pinfunction "SCL_4") (pintype "passive"))
      (node (ref "Q13") (pin "2") (pinfunction "S_2") (pintype "bidirectional"))
      (node (ref "R27") (pin "1") (pinfunction "1_1") (pintype "passive"))
    )
    (net (code "67") (name "Net-(J1-SDA)") (class "Default")
      (node (ref "J1") (pin "3") (pinfunction "SDA_3") (pintype "passive"))
      (node (ref "Q14") (pin "2") (pinfunction "S_2") (pintype "bidirectional"))
      (node (ref "R28") (pin "1") (pinfunction "1_1") (pintype "passive"))
    )
    (net (code "68") (name "VCC") (class "Default")
      (node (ref "B1") (pin "5V") (pinfunction "5V_5V") (pintype "bidirectional"))
      (node (ref "B1") (pin "IOREF") (pinfunction "IOREF_IOREF") (pintype "bidirectional"))
      (node (ref "B1") (pin "VCC") (pinfunction "VCC_VCC") (pintype "bidirectional"))
      (node (ref "D10") (pin "A") (pinfunction "A_A") (pintype "passive"))
      (node (ref "D11") (pin "A") (pinfunction "A_A") (pintype "passive"))
      (node (ref "D12") (pin "A") (pinfunction "A_A") (pintype "passive"))
      (node (ref "D13") (pin "A") (pinfunction "A_A") (pintype "passive"))
      (node (ref "D14") (pin "A") (pinfunction "A_A") (pintype "passive"))
      (node (ref "D2") (pin "A") (pinfunction "A_A") (pintype "passive"))
      (node (ref "D3") (pin "A") (pinfunction "A_A") (pintype "passive"))
      (node (ref "D4") (pin "A") (pinfunction "A_A") (pintype "passive"))
      (node (ref "D5") (pin "A") (pinfunction "A_A") (pintype "passive"))
      (node (ref "D6") (pin "A") (pinfunction "A_A") (pintype "passive"))
      (node (ref "D7") (pin "A") (pinfunction "A_A") (pintype "passive"))
      (node (ref "D8") (pin "A") (pinfunction "A_A") (pintype "passive"))
      (node (ref "D9") (pin "A") (pinfunction "A_A") (pintype "passive"))
      (node (ref "J3") (pin "20") (pinfunction "20_20") (pintype "passive"))
      (node (ref "R29") (pin "2") (pinfunction "2_2") (pintype "passive"))
      (node (ref "R30") (pin "2") (pinfunction "2_2") (pintype "passive"))
      (node (ref "S1") (pin "3") (pinfunction "S_3") (pintype "passive"))
    )
    (net (code "69") (name "VIN") (class "Default")
      (node (ref "B1") (pin "VIN") (pinfunction "VIN_VIN") (pintype "bidirectional"))
      (node (ref "C1") (pin "1") (pinfunction "+_1") (pintype "passive"))
      (node (ref "D1") (pin "C") (pinfunction "C_C") (pintype "passive"))
      (node (ref "VR1") (pin "IN") (pinfunction "IN_IN") (pintype "input"))
    )
    (net (code "70") (name "unconnected-(J2-Pad20)") (class "Default")
      (node (ref "J2") (pin "20") (pinfunction "20_20") (pintype "passive"))
    )
    (net (code "71") (name "unconnected-(J3-Pad13)") (class "Default")
      (node (ref "J3") (pin "13") (pinfunction "13_13") (pintype "passive"))
    )
    (net (code "72") (name "unconnected-(J3-Pad15)") (class "Default")
      (node (ref "J3") (pin "15") (pinfunction "15_15") (pintype "passive"))
    )
    (net (code "73") (name "unconnected-(J3-Pad16)") (class "Default")
      (node (ref "J3") (pin "16") (pinfunction "16_16") (pintype "passive"))
    )
    (net (code "74") (name "unconnected-(S1A-O-Pad1)") (class "Default")
      (node (ref "S1") (pin "1") (pinfunction "O_1") (pintype "passive"))
    )
    (net (code "75") (name "unconnected-(S1B-MT-PadMT1)") (class "Default")
      (node (ref "S1") (pin "MT1") (pinfunction "MT_MT1") (pintype "passive"))
    )
    (net (code "76") (name "unconnected-(S1C-MT-PadMT2)") (class "Default")
      (node (ref "S1") (pin "MT2") (pinfunction "MT_MT2") (pintype "passive"))
    )
    (net (code "77") (name "unconnected-(S2-Pad3)") (class "Default")
      (node (ref "S2") (pin "3") (pinfunction "3_3") (pintype "bidirectional"))
    )
    (net (code "78") (name "unconnected-(S2-Pad6)") (class "Default")
      (node (ref "S2") (pin "6") (pinfunction "6_6") (pintype "bidirectional"))
    )
  )
)
